# MCU.net
KiCad netlist of a schematic drawn in Altium Designer
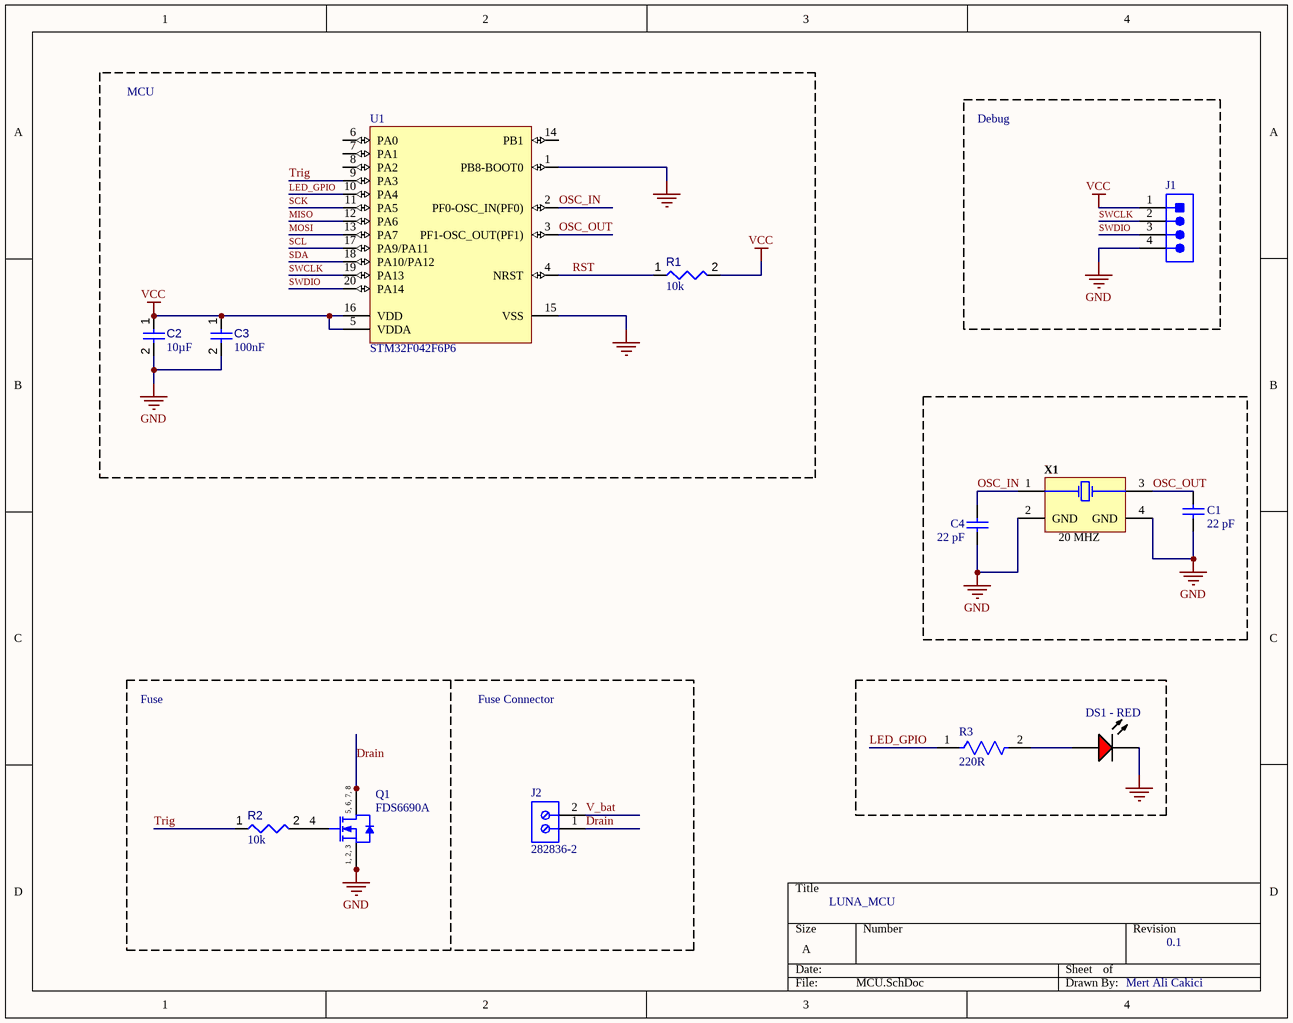
[diagram p0: MCU.SchDoc]

(export (version "E")
  (design (tool "Eeschema 10.0.6"))
  (components
    (comp (ref "C1")
      (value "22 pF")
      (footprint "CAPC1608X90X35NL10T15")
      (description "Chip Capacitor, 22 pF, +/- 5%, 50 V, -55 to 125 degC, 0603 (1608 Metric), RoHS, Tape and Reel")
      (fields (field (name "MANUFACTURER") "Murata"))
      (libsource (lib "Altium Content Vault") (part "CAP-NP-2"))
    )
    (comp (ref "C2")
      (value "10µF")
      (footprint "CAPC0603(1608)100_L")
      (description "Chip Capacitor, 10µF +/-20%, 10V, 0603, Thickness 1 mm")
      (fields (field (name "TOLERANCE") "10%") (field (name "Comment") "Capacitor 10µF +/-20% 10V 0603"))
      (libsource (lib "Mert ALi Çakıcı") (part "CAP-NP-2"))
    )
    (comp (ref "C3")
      (value "100nF")
      (footprint "CAPC1608X90X40NL10T20")
      (description "Chip Capacitor, 100 nF, +/- 10%, 50 V, 0603 (1608 Metric)")
      (fields (field (name "TOLERANCE") "10%") (field (name "Comment") "Capacitor 100 nF +/-10% 50 V 0603"))
      (libsource (lib "Mert ALi Çakıcı") (part "CAP-NP-2"))
    )
    (comp (ref "C4")
      (value "22 pF")
      (footprint "CAPC1608X90X35NL10T15")
      (description "Chip Capacitor, 22 pF, +/- 5%, 50 V, -55 to 125 degC, 0603 (1608 Metric), RoHS, Tape and Reel")
      (fields (field (name "MANUFACTURER") "Murata"))
      (libsource (lib "Altium Content Vault") (part "CAP-NP-2"))
    )
    (comp (ref "DS1 - RED")
      (value "19-217/R6C-AL1M2VY/3T")
      (footprint "EVRL-0603-2_V")
      (description "Chip LED, Red, 5 V, 25 mA, -40 to 85 degC, 2-Pin SMD (0603), RoHS, Tape and Reel")
      (fields (field (name "MANUFACTURER") "Everlight Electronics"))
      (libsource (lib "Mert ALi Çakıcı") (part "LED-RED-AK-2"))
    )
    (comp (ref "J1")
      (value "640456-4")
      (footprint "TECO-640456-4")
      (description "Male Header, Pitch 2.54 mm, 1 x 4 Position, Height 10.03 mm, Tail Length 3.56 mm, RoHS, Bulk")
      (fields (field (name "MANUFACTURER") "TE Connectivity"))
      (libsource (lib "Altium Content Vault") (part "CN-1P-M-R4"))
    )
    (comp (ref "J2")
      (value "282836-2")
      (footprint "TECO-282836-2_V")
      (description "Female Header, Pitch 5 mm, 1 x 2 Position, Height 10 mm, Tail Length 3.5 mm, Rohs, Bulk")
      (fields (field (name "VOLTAGE") "300V") (field (name "MANUFACTURER") "TE Connectivity"))
      (libsource (lib "Altium Content Vault") (part "CN-1P-F-TB2"))
    )
    (comp (ref "Q1")
      (value "FDS6690A")
      (footprint "FAIR-SOIC-8_V")
      (fields (field (name "MANUFACTURER") "Fairchild Semiconductor"))
      (libsource (lib "Altium Content Vault") (part "NEMOS-SSSGDDDD-8"))
    )
    (comp (ref "R1")
      (value "10k")
      (footprint "RESC1608X55X25NL10T15")
      (description "Chip Resistor, 10 KOhm, +/- 1%, 01 W, -55 to 155 degC, 0603 (1608 Metric)")
      (fields (field (name "POWER") "100mW") (field (name "TOLERANCE") "1%"))
      (libsource (lib "Mert ALi Çakıcı") (part "RES-2"))
    )
    (comp (ref "R2")
      (value "10k")
      (footprint "RESC1608X55X25NL10T15")
      (description "Chip Resistor, 10 KOhm, +/- 1%, 01 W, -55 to 155 degC, 0603 (1608 Metric)")
      (fields (field (name "POWER") "100mW") (field (name "TOLERANCE") "1%"))
      (libsource (lib "Mert ALi Çakıcı") (part "RES-2"))
    )
    (comp (ref "R3")
      (value "220R")
      (footprint "FP-CRCW0603-e3-MFG")
      (description "RES Thick Film, 220Ω, 1%, 0.1W, 100ppm/°C, 0603")
      (fields (field (name "TOLERANCE") "1%"))
      (libsource (lib "Altium Content Vault") (part "1029c3af85768c4190bb7ad29bc67b5"))
    )
    (comp (ref "U1")
      (value "STM32F042F6P6")
      (footprint "STM-TSSOP20_M")
      (fields (field (name "MANUFACTURER") "STMicroelectronics"))
      (libsource (lib "Altium Content Vault") (part "MC-ARM-STM32F042-TSSOP20"))
    )
    (comp (ref "X1")
      (value "20 MHZ")
      (footprint "TXC-7B-4_V")
      (fields (field (name "TOLERANCE") "30ppm") (field (name "MANUFACTURER") "TXC"))
      (libsource (lib "Mert ALi Çakıcı") (part "XTAL-1-3-4"))
    )
  )
  (nets
    (net (code "1") (name "/Drain") (class "Default")
      (node (ref "J2") (pin "1") (pinfunction "1_1") (pintype "passive"))
      (node (ref "Q1") (pin "5") (pinfunction "D_5") (pintype "passive"))
      (node (ref "Q1") (pin "6") (pinfunction "D_6") (pintype "passive"))
      (node (ref "Q1") (pin "7") (pinfunction "D_7") (pintype "passive"))
      (node (ref "Q1") (pin "8") (pinfunction "D_8") (pintype "passive"))
    )
    (net (code "2") (name "/LED_GPIO") (class "Default")
      (node (ref "R3") (pin "1") (pinfunction "1_1") (pintype "passive"))
      (node (ref "U1") (pin "10") (pinfunction "PA4_10") (pintype "bidirectional"))
    )
    (net (code "3") (name "/MISO") (class "Default")
      (node (ref "U1") (pin "12") (pinfunction "PA6_12") (pintype "bidirectional"))
    )
    (net (code "4") (name "/MOSI") (class "Default")
      (node (ref "U1") (pin "13") (pinfunction "PA7_13") (pintype "bidirectional"))
    )
    (net (code "5") (name "/OSC_IN") (class "Default")
      (node (ref "C4") (pin "2") (pinfunction "2_2") (pintype "passive"))
      (node (ref "U1") (pin "2") (pinfunction "PF0-OSC_IN(PF0)_2") (pintype "bidirectional"))
      (node (ref "X1") (pin "1") (pinfunction "X1_1") (pintype "passive"))
    )
    (net (code "6") (name "/OSC_OUT") (class "Default")
      (node (ref "C1") (pin "2") (pinfunction "2_2") (pintype "passive"))
      (node (ref "U1") (pin "3") (pinfunction "PF1-OSC_OUT(PF1)_3") (pintype "bidirectional"))
      (node (ref "X1") (pin "3") (pinfunction "X2_3") (pintype "passive"))
    )
    (net (code "7") (name "/RST") (class "Default")
      (node (ref "R1") (pin "1") (pinfunction "1_1") (pintype "passive"))
      (node (ref "U1") (pin "4") (pinfunction "NRST_4") (pintype "bidirectional"))
    )
    (net (code "8") (name "/SCK") (class "Default")
      (node (ref "U1") (pin "11") (pinfunction "PA5_11") (pintype "bidirectional"))
    )
    (net (code "9") (name "/SCL") (class "Default")
      (node (ref "U1") (pin "17") (pinfunction "PA9/PA11_17") (pintype "bidirectional"))
    )
    (net (code "10") (name "/SDA") (class "Default")
      (node (ref "U1") (pin "18") (pinfunction "PA10/PA12_18") (pintype "bidirectional"))
    )
    (net (code "11") (name "/SWCLK") (class "Default")
      (node (ref "J1") (pin "2") (pinfunction "2_2") (pintype "passive"))
      (node (ref "U1") (pin "19") (pinfunction "PA13_19") (pintype "bidirectional"))
    )
    (net (code "12") (name "/SWDIO") (class "Default")
      (node (ref "J1") (pin "3") (pinfunction "3_3") (pintype "passive"))
      (node (ref "U1") (pin "20") (pinfunction "PA14_20") (pintype "bidirectional"))
    )
    (net (code "13") (name "/Trig") (class "Default")
      (node (ref "R2") (pin "1") (pinfunction "1_1") (pintype "passive"))
      (node (ref "U1") (pin "9") (pinfunction "PA3_9") (pintype "bidirectional"))
    )
    (net (code "14") (name "/V_bat") (class "Default")
      (node (ref "J2") (pin "2") (pinfunction "2_2") (pintype "passive"))
    )
    (net (code "15") (name "GND") (class "Default")
      (node (ref "C1") (pin "1") (pinfunction "1_1") (pintype "passive"))
      (node (ref "C2") (pin "2") (pinfunction "2_2") (pintype "passive"))
      (node (ref "C3") (pin "2") (pinfunction "2_2") (pintype "passive"))
      (node (ref "C4") (pin "1") (pinfunction "1_1") (pintype "passive"))
      (node (ref "DS1 - RED") (pin "2") (pinfunction "K_2") (pintype "passive"))
      (node (ref "J1") (pin "4") (pinfunction "4_4") (pintype "passive"))
      (node (ref "Q1") (pin "1") (pinfunction "S_1") (pintype "passive"))
      (node (ref "Q1") (pin "2") (pinfunction "S_2") (pintype "passive"))
      (node (ref "Q1") (pin "3") (pinfunction "S_3") (pintype "passive"))
      (node (ref "U1") (pin "1") (pinfunction "PB8-BOOT0_1") (pintype "bidirectional"))
      (node (ref "U1") (pin "15") (pinfunction "VSS_15") (pintype "power_in"))
      (node (ref "X1") (pin "2") (pinfunction "GND_2") (pintype "power_in"))
      (node (ref "X1") (pin "4") (pinfunction "GND_4") (pintype "power_in"))
    )
    (net (code "16") (name "Net-(DS1 - RED-A)") (class "Default")
      (node (ref "DS1 - RED") (pin "1") (pinfunction "A_1") (pintype "passive"))
      (node (ref "R3") (pin "2") (pinfunction "2_2") (pintype "passive"))
    )
    (net (code "17") (name "Net-(Q1-G)") (class "Default")
      (node (ref "Q1") (pin "4") (pinfunction "G_4") (pintype "passive"))
      (node (ref "R2") (pin "2") (pinfunction "2_2") (pintype "passive"))
    )
    (net (code "18") (name "VCC") (class "Default")
      (node (ref "C2") (pin "1") (pinfunction "1_1") (pintype "passive"))
      (node (ref "C3") (pin "1") (pinfunction "1_1") (pintype "passive"))
      (node (ref "J1") (pin "1") (pinfunction "1_1") (pintype "passive"))
      (node (ref "R1") (pin "2") (pinfunction "2_2") (pintype "passive"))
      (node (ref "U1") (pin "16") (pinfunction "VDD_16") (pintype "power_in"))
      (node (ref "U1") (pin "5") (pinfunction "VDDA_5") (pintype "power_in"))
    )
    (net (code "19") (name "unconnected-(U1-PA0-Pad6)") (class "Default")
      (node (ref "U1") (pin "6") (pinfunction "PA0_6") (pintype "bidirectional"))
    )
    (net (code "20") (name "unconnected-(U1-PA1-Pad7)") (class "Default")
      (node (ref "U1") (pin "7") (pinfunction "PA1_7") (pintype "bidirectional"))
    )
    (net (code "21") (name "unconnected-(U1-PA2-Pad8)") (class "Default")
      (node (ref "U1") (pin "8") (pinfunction "PA2_8") (pintype "bidirectional"))
    )
    (net (code "22") (name "unconnected-(U1-PB1-Pad14)") (class "Default")
      (node (ref "U1") (pin "14") (pinfunction "PB1_14") (pintype "bidirectional"))
    )
  )
)
